# DSM_VB2032-241203_Sch.net
KiCad netlist of a schematic drawn in Altium Designer
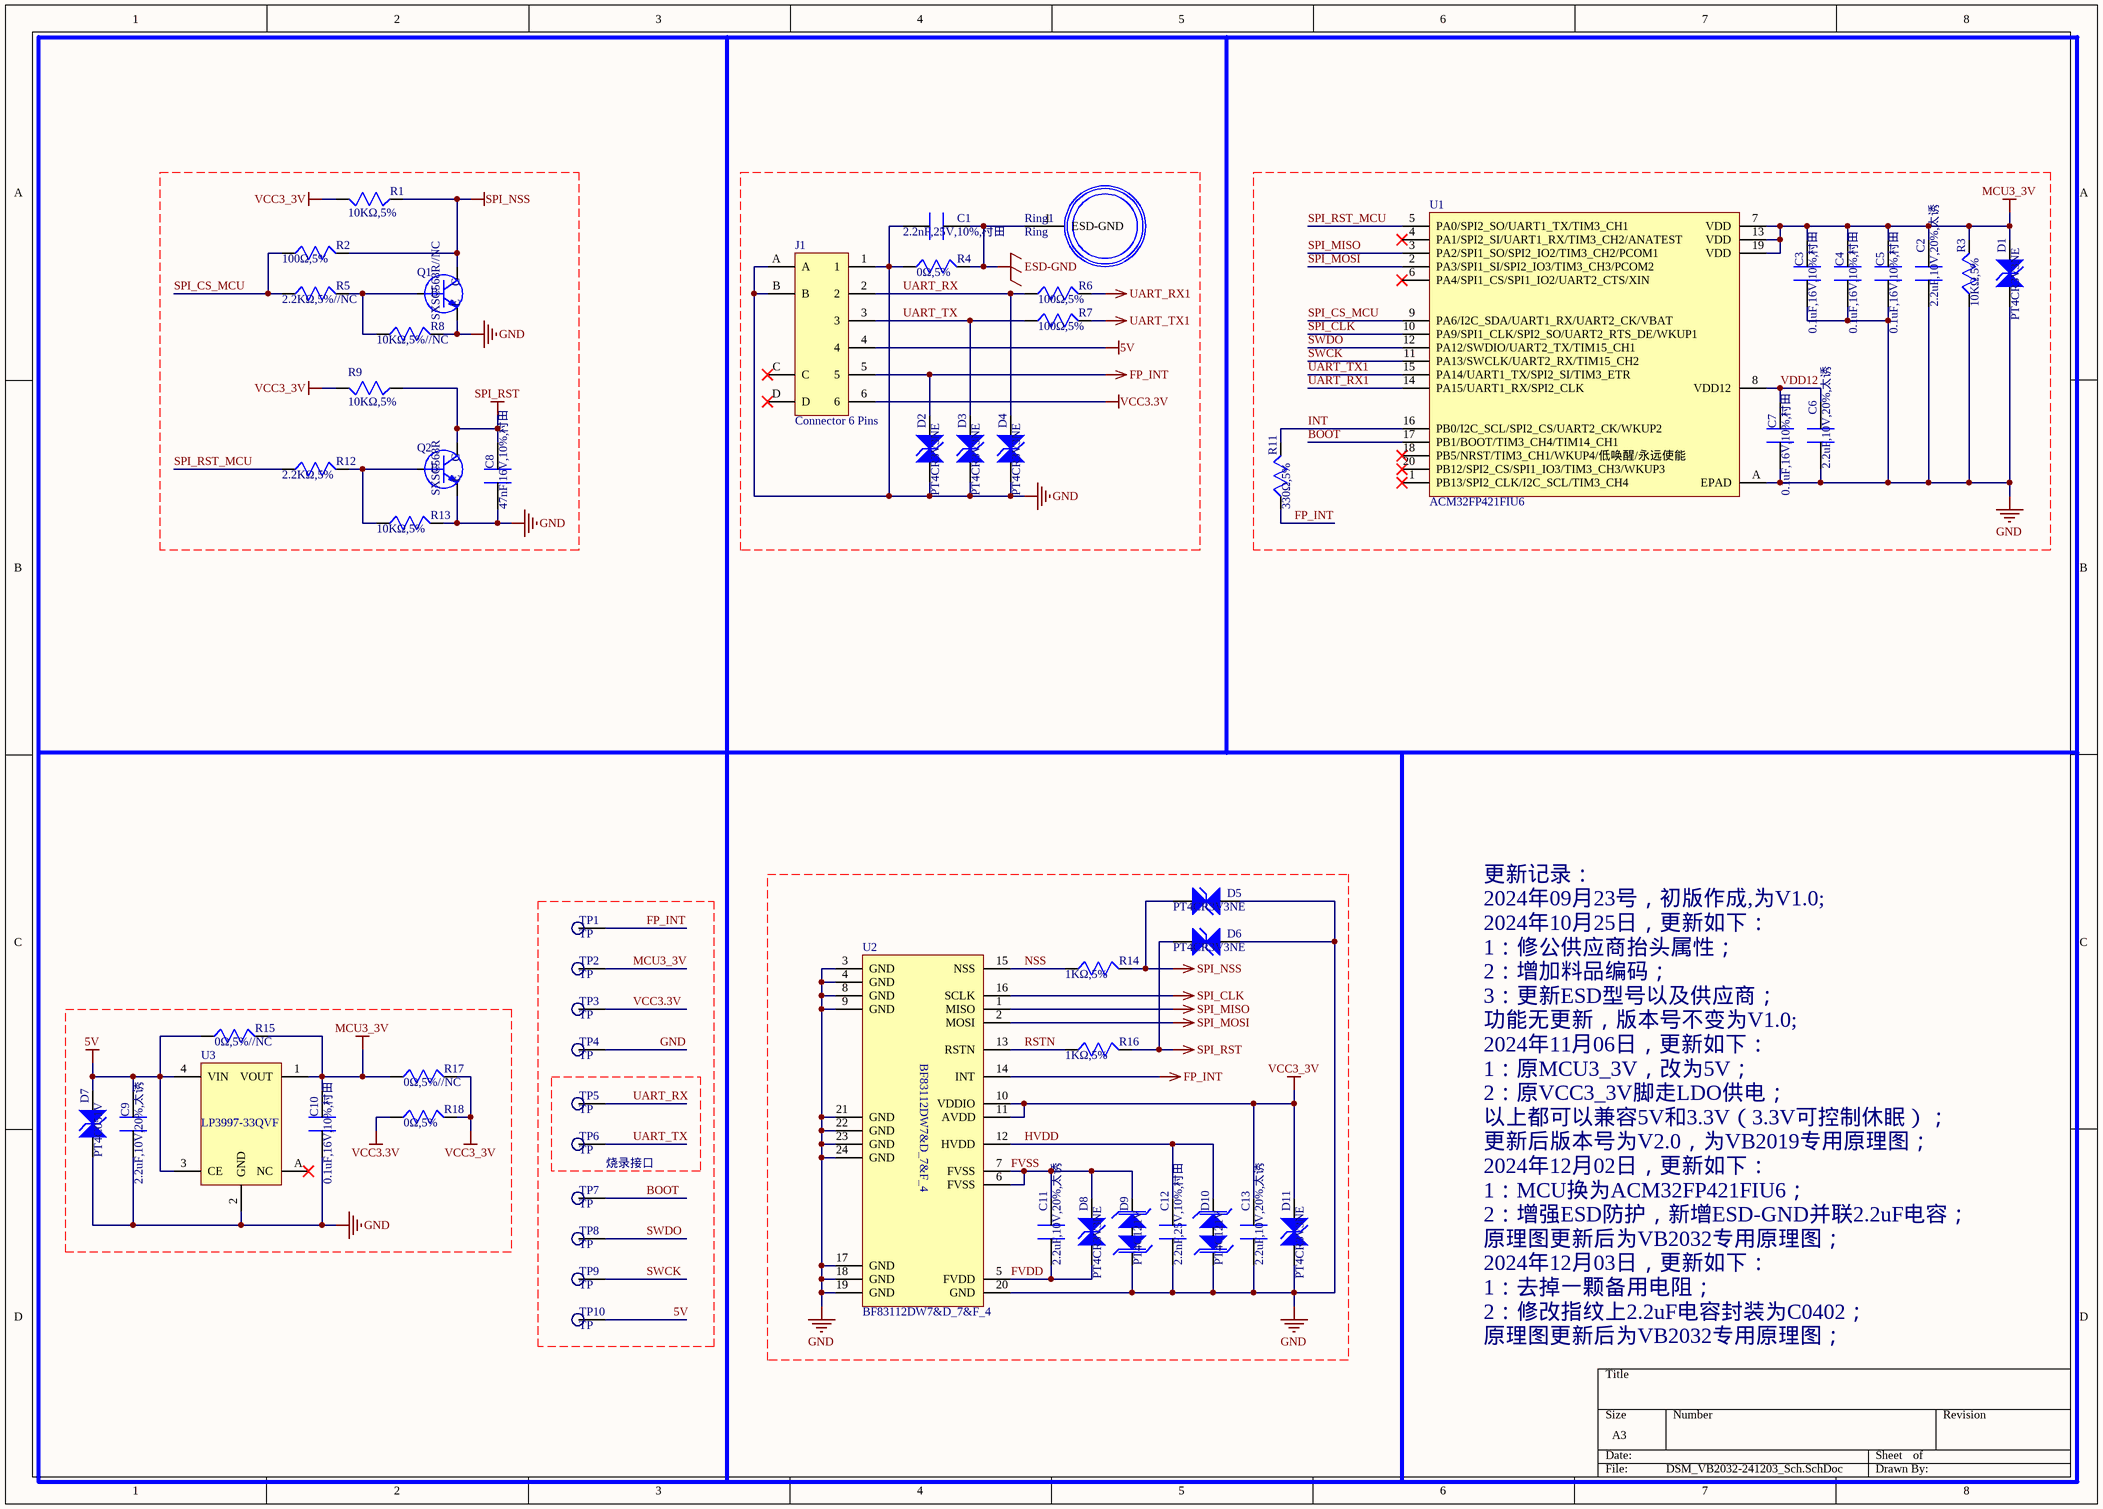
[diagram p0: DSM_VB2032-241203_Sch.SchDoc]

(export (version "E")
  (design (tool "Eeschema 10.0.6"))
  (components
    (comp (ref "C1")
      (value "2.2nF,25V,10%,村田")
      (footprint "C0201")
      (description "贴片电容")
      (libsource (lib "Mkyou") (part "Cap"))
    )
    (comp (ref "C2")
      (value "2.2uF,10V,20%,太诱")
      (footprint "C0201")
      (description "贴片电容")
      (libsource (lib "Mkyou") (part "Cap"))
    )
    (comp (ref "C3")
      (value "0.1uF,16V,10%,村田")
      (footprint "C0201")
      (description "贴片电容")
      (libsource (lib "Mkyou") (part "Cap"))
    )
    (comp (ref "C4")
      (value "0.1uF,16V,10%,村田")
      (footprint "C0201")
      (description "贴片电容")
      (libsource (lib "Mkyou") (part "Cap"))
    )
    (comp (ref "C5")
      (value "0.1uF,16V,10%,村田")
      (footprint "C0201")
      (description "贴片电容")
      (libsource (lib "Mkyou") (part "Cap"))
    )
    (comp (ref "C6")
      (value "2.2uF,10V,20%,太诱")
      (footprint "C0201")
      (description "贴片电容")
      (libsource (lib "Mkyou") (part "Cap"))
    )
    (comp (ref "C7")
      (value "0.1uF,16V,10%,村田")
      (footprint "C0201")
      (description "贴片电容")
      (libsource (lib "Mkyou") (part "Cap"))
    )
    (comp (ref "C8")
      (value "47nF,16V,10%,村田")
      (footprint "C0201")
      (description "贴片电容")
      (libsource (lib "Mkyou") (part "Cap"))
    )
    (comp (ref "C9")
      (value "2.2uF,10V,20%,太诱")
      (footprint "C0201")
      (description "贴片电容")
      (libsource (lib "Mkyou") (part "Cap"))
    )
    (comp (ref "C10")
      (value "0.1uF,16V,10%,村田")
      (footprint "C0201")
      (description "贴片电容")
      (libsource (lib "Mkyou") (part "Cap"))
    )
    (comp (ref "C11")
      (value "2.2uF,10V,20%,太诱")
      (footprint "CC0402-M")
      (description "贴片电容")
      (libsource (lib "Mkyou") (part "Cap"))
    )
    (comp (ref "C12")
      (value "2.2nF,25V,10%,村田")
      (footprint "C0201")
      (description "贴片电容")
      (libsource (lib "Mkyou") (part "Cap"))
    )
    (comp (ref "C13")
      (value "2.2uF,10V,20%,太诱")
      (footprint "CC0402-M")
      (description "贴片电容")
      (libsource (lib "Mkyou") (part "Cap"))
    )
    (comp (ref "D1")
      (value "PT4CR3V3NE")
      (footprint "SOD-962")
      (description "双向静电二极管")
      (libsource (lib "Mkyou") (part "ESD"))
    )
    (comp (ref "D2")
      (value "PT4CR3V3NE")
      (footprint "SOD-962")
      (description "双向静电二极管")
      (libsource (lib "Mkyou") (part "ESD"))
    )
    (comp (ref "D3")
      (value "PT4CR3V3NE")
      (footprint "SOD-962")
      (description "双向静电二极管")
      (libsource (lib "Mkyou") (part "ESD"))
    )
    (comp (ref "D4")
      (value "PT4CR3V3NE")
      (footprint "SOD-962")
      (description "双向静电二极管")
      (libsource (lib "Mkyou") (part "ESD"))
    )
    (comp (ref "D5")
      (value "PT4CR3V3NE")
      (footprint "SOD-962")
      (description "双向静电二极管")
      (libsource (lib "Mkyou") (part "ESD"))
    )
    (comp (ref "D6")
      (value "PT4CR3V3NE")
      (footprint "SOD-962")
      (description "双向静电二极管")
      (libsource (lib "Mkyou") (part "ESD"))
    )
    (comp (ref "D7")
      (value "PT4C051V")
      (footprint "DFN0603-2L 0.3*0.23 Pitch 0.38")
      (description "双向静电二极管")
      (libsource (lib "Mkyou") (part "ESD"))
    )
    (comp (ref "D8")
      (value "PT4CR3V3NE")
      (footprint "SOD-962")
      (description "双向静电二极管")
      (libsource (lib "Mkyou") (part "ESD"))
    )
    (comp (ref "D9")
      (value "PT4C121V")
      (footprint "SOD-962")
      (description "双向瞬态抑制二极管")
      (libsource (lib "Mkyou") (part "TVS"))
    )
    (comp (ref "D10")
      (value "PT4C121V")
      (footprint "SOD-962")
      (description "双向瞬态抑制二极管")
      (libsource (lib "Mkyou") (part "TVS"))
    )
    (comp (ref "D11")
      (value "PT4CR3V3NE")
      (footprint "SOD-962")
      (description "双向静电二极管")
      (libsource (lib "Mkyou") (part "ESD"))
    )
    (comp (ref "J1")
      (value "Connector 6 Pins")
      (footprint "A1004LF-06A")
      (description "连接器")
      (libsource (lib "Mkyou") (part "Connector 6 Pins"))
    )
    (comp (ref "Q1")
      (value "SXSC568R//NC")
      (footprint "SOT-723")
      (description "NPN型三极管")
      (libsource (lib "Mkyou") (part "NPN BCE"))
    )
    (comp (ref "Q2")
      (value "SXSC568R")
      (footprint "SOT-723")
      (description "NPN型三极管")
      (libsource (lib "Mkyou") (part "NPN BCE"))
    )
    (comp (ref "R1")
      (value "10KΩ,5%")
      (footprint "R0201")
      (description "贴片电阻")
      (libsource (lib "Mkyou") (part "RES"))
    )
    (comp (ref "R2")
      (value "100Ω,5%")
      (footprint "R0201")
      (description "贴片电阻")
      (libsource (lib "Mkyou") (part "RES"))
    )
    (comp (ref "R3")
      (value "10KΩ,5%")
      (footprint "R0201")
      (description "贴片电阻")
      (libsource (lib "Mkyou") (part "RES"))
    )
    (comp (ref "R4")
      (value "0Ω,5%")
      (footprint "R0201")
      (description "贴片电阻")
      (libsource (lib "Mkyou") (part "RES"))
    )
    (comp (ref "R5")
      (value "2.2KΩ,5%//NC")
      (footprint "R0201")
      (description "贴片电阻")
      (libsource (lib "Mkyou") (part "RES"))
    )
    (comp (ref "R6")
      (value "100Ω,5%")
      (footprint "R0201")
      (description "贴片电阻")
      (libsource (lib "Mkyou") (part "RES"))
    )
    (comp (ref "R7")
      (value "100Ω,5%")
      (footprint "R0201")
      (description "贴片电阻")
      (libsource (lib "Mkyou") (part "RES"))
    )
    (comp (ref "R8")
      (value "10KΩ,5%//NC")
      (footprint "R0201")
      (description "贴片电阻")
      (libsource (lib "Mkyou") (part "RES"))
    )
    (comp (ref "R9")
      (value "10KΩ,5%")
      (footprint "R0201")
      (description "贴片电阻")
      (libsource (lib "Mkyou") (part "RES"))
    )
    (comp (ref "R11")
      (value "330Ω,5%")
      (footprint "R0201")
      (description "贴片电阻")
      (libsource (lib "Mkyou") (part "RES"))
    )
    (comp (ref "R12")
      (value "2.2KΩ,5%")
      (footprint "R0201")
      (description "贴片电阻")
      (libsource (lib "Mkyou") (part "RES"))
    )
    (comp (ref "R13")
      (value "10KΩ,5%")
      (footprint "R0201")
      (description "贴片电阻")
      (libsource (lib "Mkyou") (part "RES"))
    )
    (comp (ref "R14")
      (value "1KΩ,5%")
      (footprint "R0201")
      (description "贴片电阻")
      (libsource (lib "Mkyou") (part "RES"))
    )
    (comp (ref "R15")
      (value "0Ω,5%//NC")
      (footprint "R0201")
      (description "贴片电阻")
      (libsource (lib "Mkyou") (part "RES"))
    )
    (comp (ref "R16")
      (value "1KΩ,5%")
      (footprint "R0201")
      (description "贴片电阻")
      (libsource (lib "Mkyou") (part "RES"))
    )
    (comp (ref "R17")
      (value "0Ω,5%//NC")
      (footprint "R0201")
      (description "贴片电阻")
      (libsource (lib "Mkyou") (part "RES"))
    )
    (comp (ref "R18")
      (value "0Ω,5%")
      (footprint "R0201")
      (description "贴片电阻")
      (libsource (lib "Mkyou") (part "RES"))
    )
    (comp (ref "Ring1")
      (value "Ring")
      (footprint "Ring")
      (description "金属环")
      (libsource (lib "Mkyou") (part "Ring"))
    )
    (comp (ref "TP1")
      (value "TP")
      (footprint "TP（Φ0.5）")
      (description "非正常物料无需采购")
      (libsource (lib "Mkyou") (part "TP"))
    )
    (comp (ref "TP2")
      (value "TP")
      (footprint "TP（Φ0.5）")
      (description "非正常物料无需采购")
      (libsource (lib "Mkyou") (part "TP"))
    )
    (comp (ref "TP3")
      (value "TP")
      (footprint "TP（Φ0.5）")
      (description "非正常物料无需采购")
      (libsource (lib "Mkyou") (part "TP"))
    )
    (comp (ref "TP4")
      (value "TP")
      (footprint "TP（Φ0.5）")
      (description "非正常物料无需采购")
      (libsource (lib "Mkyou") (part "TP"))
    )
    (comp (ref "TP5")
      (value "TP")
      (footprint "TP（Φ0.5）")
      (description "非正常物料无需采购")
      (libsource (lib "Mkyou") (part "TP"))
    )
    (comp (ref "TP6")
      (value "TP")
      (footprint "TP（Φ0.5）")
      (description "非正常物料无需采购")
      (libsource (lib "Mkyou") (part "TP"))
    )
    (comp (ref "TP7")
      (value "TP")
      (footprint "TP（Φ0.5）")
      (description "非正常物料无需采购")
      (libsource (lib "Mkyou") (part "TP"))
    )
    (comp (ref "TP8")
      (value "TP")
      (footprint "TP（Φ0.5）")
      (description "非正常物料无需采购")
      (libsource (lib "Mkyou") (part "TP"))
    )
    (comp (ref "TP9")
      (value "TP")
      (footprint "TP（Φ0.5）")
      (description "非正常物料无需采购")
      (libsource (lib "Mkyou") (part "TP"))
    )
    (comp (ref "TP10")
      (value "TP")
      (footprint "TP（Φ0.5）")
      (description "非正常物料无需采购")
      (libsource (lib "Mkyou") (part "TP"))
    )
    (comp (ref "U1")
      (value "ACM32FP421FIU6")
      (footprint "QFN 20 3*3 Pitch 0.4")
      (description "微控制单元")
      (libsource (lib "Mkyou") (part "ACM32FP421"))
    )
    (comp (ref "U2")
      (value "BF83112DW7&D_7&F_4")
      (footprint "BF83112DW7&D_7&F_4")
      (description "电容按压式指纹识别芯片")
      (libsource (lib "Mkyou") (part "BF83112DW7&D_7&F_4"))
    )
    (comp (ref "U3")
      (value "LP3997-33QVF")
      (footprint "DFN 1*1-4L")
      (description "线性稳压器")
      (libsource (lib "Mkyou") (part "LDO 4 Pins"))
    )
  )
  (nets
    (net (code "1") (name "/BOOT") (class "Default")
      (node (ref "TP7") (pin "1") (pinfunction "1_1") (pintype "passive"))
      (node (ref "U1") (pin "17") (pinfunction "PB1/BOOT/TIM3_CH4/TIM14_CH1_17") (pintype "passive"))
    )
    (net (code "2") (name "/FVDD") (class "Default")
      (node (ref "C11") (pin "1") (pinfunction "1_1") (pintype "passive"))
      (node (ref "D8") (pin "1") (pinfunction "1_1") (pintype "passive"))
      (node (ref "U2") (pin "5") (pinfunction "FVDD_5") (pintype "passive"))
    )
    (net (code "3") (name "/FVSS") (class "Default")
      (node (ref "C11") (pin "2") (pinfunction "2_2") (pintype "passive"))
      (node (ref "D8") (pin "2") (pinfunction "2_2") (pintype "passive"))
      (node (ref "D9") (pin "1") (pinfunction "1_1") (pintype "passive"))
      (node (ref "U2") (pin "6") (pinfunction "FVSS_6") (pintype "passive"))
      (node (ref "U2") (pin "7") (pinfunction "FVSS_7") (pintype "passive"))
    )
    (net (code "4") (name "/HVDD") (class "Default")
      (node (ref "C12") (pin "2") (pinfunction "2_2") (pintype "passive"))
      (node (ref "D10") (pin "1") (pinfunction "1_1") (pintype "passive"))
      (node (ref "U2") (pin "12") (pinfunction "HVDD_12") (pintype "passive"))
    )
    (net (code "5") (name "/INT") (class "Default")
      (node (ref "R11") (pin "2") (pinfunction "2_2") (pintype "passive"))
      (node (ref "U1") (pin "16") (pinfunction "PB0/I2C_SCL/SPI2_CS/UART2_CK/WKUP2_16") (pintype "passive"))
    )
    (net (code "6") (name "/NSS") (class "Default")
      (node (ref "R14") (pin "1") (pinfunction "1_1") (pintype "passive"))
      (node (ref "U2") (pin "15") (pinfunction "NSS_15") (pintype "passive"))
    )
    (net (code "7") (name "/RSTN") (class "Default")
      (node (ref "R16") (pin "1") (pinfunction "1_1") (pintype "passive"))
      (node (ref "U2") (pin "13") (pinfunction "RSTN_13") (pintype "passive"))
    )
    (net (code "8") (name "/SPI_CS_MCU") (class "Default")
      (node (ref "R2") (pin "1") (pinfunction "1_1") (pintype "passive"))
      (node (ref "R5") (pin "1") (pinfunction "1_1") (pintype "passive"))
      (node (ref "U1") (pin "9") (pinfunction "PA6/I2C_SDA/UART1_RX/UART2_CK/VBAT_9") (pintype "passive"))
    )
    (net (code "9") (name "/SPI_RST_MCU") (class "Default")
      (node (ref "R12") (pin "1") (pinfunction "1_1") (pintype "passive"))
      (node (ref "U1") (pin "5") (pinfunction "PA0/SPI2_SO/UART1_TX/TIM3_CH1_5") (pintype "passive"))
    )
    (net (code "10") (name "/SWCK") (class "Default")
      (node (ref "TP9") (pin "1") (pinfunction "1_1") (pintype "passive"))
      (node (ref "U1") (pin "11") (pinfunction "PA13/SWCLK/UART2_RX/TIM15_CH2_11") (pintype "passive"))
    )
    (net (code "11") (name "/SWDO") (class "Default")
      (node (ref "TP8") (pin "1") (pinfunction "1_1") (pintype "passive"))
      (node (ref "U1") (pin "12") (pinfunction "PA12/SWDIO/UART2_TX/TIM15_CH1_12") (pintype "passive"))
    )
    (net (code "12") (name "/UART_RX") (class "Default")
      (node (ref "D4") (pin "2") (pinfunction "2_2") (pintype "passive"))
      (node (ref "J1") (pin "2") (pinfunction "2_2") (pintype "passive"))
      (node (ref "R6") (pin "1") (pinfunction "1_1") (pintype "passive"))
      (node (ref "TP5") (pin "1") (pinfunction "1_1") (pintype "passive"))
    )
    (net (code "13") (name "/UART_TX") (class "Default")
      (node (ref "D3") (pin "2") (pinfunction "2_2") (pintype "passive"))
      (node (ref "J1") (pin "3") (pinfunction "3_3") (pintype "passive"))
      (node (ref "R7") (pin "1") (pinfunction "1_1") (pintype "passive"))
      (node (ref "TP6") (pin "1") (pinfunction "1_1") (pintype "passive"))
    )
    (net (code "14") (name "/VDD12") (class "Default")
      (node (ref "C6") (pin "2") (pinfunction "2_2") (pintype "passive"))
      (node (ref "C7") (pin "2") (pinfunction "2_2") (pintype "passive"))
      (node (ref "U1") (pin "8") (pinfunction "VDD12_8") (pintype "passive"))
    )
    (net (code "15") (name "5V") (class "Default")
      (node (ref "C9") (pin "2") (pinfunction "2_2") (pintype "passive"))
      (node (ref "D7") (pin "2") (pinfunction "2_2") (pintype "passive"))
      (node (ref "J1") (pin "4") (pinfunction "4_4") (pintype "passive"))
      (node (ref "R15") (pin "1") (pinfunction "1_1") (pintype "passive"))
      (node (ref "TP10") (pin "1") (pinfunction "1_1") (pintype "passive"))
      (node (ref "U3") (pin "3") (pinfunction "CE_3") (pintype "passive"))
      (node (ref "U3") (pin "4") (pinfunction "VIN_4") (pintype "passive"))
    )
    (net (code "16") (name "ESD-GND") (class "Default")
      (node (ref "C1") (pin "1") (pinfunction "1_1") (pintype "passive"))
      (node (ref "R4") (pin "2") (pinfunction "2_2") (pintype "passive"))
      (node (ref "Ring1") (pin "1") (pinfunction "ESD-GND_1") (pintype "passive"))
    )
    (net (code "17") (name "FP_INT") (class "Default")
      (node (ref "D2") (pin "2") (pinfunction "2_2") (pintype "passive"))
      (node (ref "J1") (pin "5") (pinfunction "5_5") (pintype "passive"))
      (node (ref "R11") (pin "1") (pinfunction "1_1") (pintype "passive"))
      (node (ref "TP1") (pin "1") (pinfunction "1_1") (pintype "passive"))
      (node (ref "U2") (pin "14") (pinfunction "INT_14") (pintype "passive"))
    )
    (net (code "18") (name "GND") (class "Default")
      (node (ref "C1") (pin "2") (pinfunction "2_2") (pintype "passive"))
      (node (ref "C10") (pin "1") (pinfunction "1_1") (pintype "passive"))
      (node (ref "C12") (pin "1") (pinfunction "1_1") (pintype "passive"))
      (node (ref "C13") (pin "1") (pinfunction "1_1") (pintype "passive"))
      (node (ref "C2") (pin "1") (pinfunction "1_1") (pintype "passive"))
      (node (ref "C3") (pin "1") (pinfunction "1_1") (pintype "passive"))
      (node (ref "C4") (pin "1") (pinfunction "1_1") (pintype "passive"))
      (node (ref "C5") (pin "1") (pinfunction "1_1") (pintype "passive"))
      (node (ref "C6") (pin "1") (pinfunction "1_1") (pintype "passive"))
      (node (ref "C7") (pin "1") (pinfunction "1_1") (pintype "passive"))
      (node (ref "C8") (pin "1") (pinfunction "1_1") (pintype "passive"))
      (node (ref "C9") (pin "1") (pinfunction "1_1") (pintype "passive"))
      (node (ref "D1") (pin "1") (pinfunction "1_1") (pintype "passive"))
      (node (ref "D10") (pin "2") (pinfunction "2_2") (pintype "passive"))
      (node (ref "D11") (pin "1") (pinfunction "1_1") (pintype "passive"))
      (node (ref "D2") (pin "1") (pinfunction "1_1") (pintype "passive"))
      (node (ref "D3") (pin "1") (pinfunction "1_1") (pintype "passive"))
      (node (ref "D4") (pin "1") (pinfunction "1_1") (pintype "passive"))
      (node (ref "D5") (pin "1") (pinfunction "1_1") (pintype "passive"))
      (node (ref "D6") (pin "1") (pinfunction "1_1") (pintype "passive"))
      (node (ref "D7") (pin "1") (pinfunction "1_1") (pintype "passive"))
      (node (ref "D9") (pin "2") (pinfunction "2_2") (pintype "passive"))
      (node (ref "J1") (pin "1") (pinfunction "1_1") (pintype "passive"))
      (node (ref "J1") (pin "A") (pinfunction "A_A") (pintype "passive"))
      (node (ref "J1") (pin "B") (pinfunction "B_B") (pintype "passive"))
      (node (ref "Q1") (pin "2") (pinfunction "E_2") (pintype "passive"))
      (node (ref "Q2") (pin "2") (pinfunction "E_2") (pintype "passive"))
      (node (ref "R13") (pin "2") (pinfunction "2_2") (pintype "passive"))
      (node (ref "R3") (pin "1") (pinfunction "1_1") (pintype "passive"))
      (node (ref "R4") (pin "1") (pinfunction "1_1") (pintype "passive"))
      (node (ref "R8") (pin "2") (pinfunction "2_2") (pintype "passive"))
      (node (ref "TP4") (pin "1") (pinfunction "1_1") (pintype "passive"))
      (node (ref "U1") (pin "A") (pinfunction "EPAD_A") (pintype "passive"))
      (node (ref "U2") (pin "17") (pinfunction "GND_17") (pintype "passive"))
      (node (ref "U2") (pin "18") (pinfunction "GND_18") (pintype "passive"))
      (node (ref "U2") (pin "19") (pinfunction "GND_19") (pintype "passive"))
      (node (ref "U2") (pin "20") (pinfunction "GND_20") (pintype "passive"))
      (node (ref "U2") (pin "21") (pinfunction "GND_21") (pintype "passive"))
      (node (ref "U2") (pin "22") (pinfunction "GND_22") (pintype "passive"))
      (node (ref "U2") (pin "23") (pinfunction "GND_23") (pintype "passive"))
      (node (ref "U2") (pin "24") (pinfunction "GND_24") (pintype "passive"))
      (node (ref "U2") (pin "3") (pinfunction "GND_3") (pintype "passive"))
      (node (ref "U2") (pin "4") (pinfunction "GND_4") (pintype "passive"))
      (node (ref "U2") (pin "8") (pinfunction "GND_8") (pintype "passive"))
      (node (ref "U2") (pin "9") (pinfunction "GND_9") (pintype "passive"))
      (node (ref "U3") (pin "2") (pinfunction "GND_2") (pintype "passive"))
    )
    (net (code "19") (name "MCU3_3V") (class "Default")
      (node (ref "C10") (pin "2") (pinfunction "2_2") (pintype "passive"))
      (node (ref "C2") (pin "2") (pinfunction "2_2") (pintype "passive"))
      (node (ref "C3") (pin "2") (pinfunction "2_2") (pintype "passive"))
      (node (ref "C4") (pin "2") (pinfunction "2_2") (pintype "passive"))
      (node (ref "C5") (pin "2") (pinfunction "2_2") (pintype "passive"))
      (node (ref "D1") (pin "2") (pinfunction "2_2") (pintype "passive"))
      (node (ref "R15") (pin "2") (pinfunction "2_2") (pintype "passive"))
      (node (ref "R17") (pin "1") (pinfunction "1_1") (pintype "passive"))
      (node (ref "R3") (pin "2") (pinfunction "2_2") (pintype "passive"))
      (node (ref "TP2") (pin "1") (pinfunction "1_1") (pintype "passive"))
      (node (ref "U1") (pin "13") (pinfunction "VDD_13") (pintype "passive"))
      (node (ref "U1") (pin "19") (pinfunction "VDD_19") (pintype "passive"))
      (node (ref "U1") (pin "7") (pinfunction "VDD_7") (pintype "passive"))
      (node (ref "U3") (pin "1") (pinfunction "VOUT_1") (pintype "passive"))
    )
    (net (code "20") (name "Net-(Q1-B)") (class "Default")
      (node (ref "Q1") (pin "1") (pinfunction "B_1") (pintype "passive"))
      (node (ref "R5") (pin "2") (pinfunction "2_2") (pintype "passive"))
      (node (ref "R8") (pin "1") (pinfunction "1_1") (pintype "passive"))
    )
    (net (code "21") (name "Net-(Q2-B)") (class "Default")
      (node (ref "Q2") (pin "1") (pinfunction "B_1") (pintype "passive"))
      (node (ref "R12") (pin "2") (pinfunction "2_2") (pintype "passive"))
      (node (ref "R13") (pin "1") (pinfunction "1_1") (pintype "passive"))
    )
    (net (code "22") (name "SPI_CLK") (class "Default")
      (node (ref "U1") (pin "10") (pinfunction "PA9/SPI1_CLK/SPI2_SO/UART2_RTS_DE/WKUP1_10") (pintype "passive"))
      (node (ref "U2") (pin "16") (pinfunction "SCLK_16") (pintype "passive"))
    )
    (net (code "23") (name "SPI_MISO") (class "Default")
      (node (ref "U1") (pin "3") (pinfunction "PA2/SPI1_SO/SPI2_IO2/TIM3_CH2/PCOM1_3") (pintype "passive"))
      (node (ref "U2") (pin "1") (pinfunction "MISO_1") (pintype "passive"))
    )
    (net (code "24") (name "SPI_MOSI") (class "Default")
      (node (ref "U1") (pin "2") (pinfunction "PA3/SPI1_SI/SPI2_IO3/TIM3_CH3/PCOM2_2") (pintype "passive"))
      (node (ref "U2") (pin "2") (pinfunction "MOSI_2") (pintype "passive"))
    )
    (net (code "25") (name "SPI_NSS") (class "Default")
      (node (ref "D5") (pin "2") (pinfunction "2_2") (pintype "passive"))
      (node (ref "Q1") (pin "3") (pinfunction "C_3") (pintype "passive"))
      (node (ref "R1") (pin "1") (pinfunction "1_1") (pintype "passive"))
      (node (ref "R14") (pin "2") (pinfunction "2_2") (pintype "passive"))
      (node (ref "R2") (pin "2") (pinfunction "2_2") (pintype "passive"))
    )
    (net (code "26") (name "SPI_RST") (class "Default")
      (node (ref "C8") (pin "2") (pinfunction "2_2") (pintype "passive"))
      (node (ref "D6") (pin "2") (pinfunction "2_2") (pintype "passive"))
      (node (ref "Q2") (pin "3") (pinfunction "C_3") (pintype "passive"))
      (node (ref "R16") (pin "2") (pinfunction "2_2") (pintype "passive"))
      (node (ref "R9") (pin "1") (pinfunction "1_1") (pintype "passive"))
    )
    (net (code "27") (name "UART_RX1") (class "Default")
      (node (ref "R6") (pin "2") (pinfunction "2_2") (pintype "passive"))
      (node (ref "U1") (pin "14") (pinfunction "PA15/UART1_RX/SPI2_CLK_14") (pintype "passive"))
    )
    (net (code "28") (name "UART_TX1") (class "Default")
      (node (ref "R7") (pin "2") (pinfunction "2_2") (pintype "passive"))
      (node (ref "U1") (pin "15") (pinfunction "PA14/UART1_TX/SPI2_SI/TIM3_ETR_15") (pintype "passive"))
    )
    (net (code "29") (name "VCC3.3V") (class "Default")
      (node (ref "J1") (pin "6") (pinfunction "6_6") (pintype "passive"))
      (node (ref "R18") (pin "1") (pinfunction "1_1") (pintype "passive"))
      (node (ref "TP3") (pin "1") (pinfunction "1_1") (pintype "passive"))
    )
    (net (code "30") (name "VCC3_3V") (class "Default")
      (node (ref "C13") (pin "2") (pinfunction "2_2") (pintype "passive"))
      (node (ref "D11") (pin "2") (pinfunction "2_2") (pintype "passive"))
      (node (ref "R1") (pin "2") (pinfunction "2_2") (pintype "passive"))
      (node (ref "R17") (pin "2") (pinfunction "2_2") (pintype "passive"))
      (node (ref "R18") (pin "2") (pinfunction "2_2") (pintype "passive"))
      (node (ref "R9") (pin "2") (pinfunction "2_2") (pintype "passive"))
      (node (ref "U2") (pin "10") (pinfunction "VDDIO_10") (pintype "passive"))
      (node (ref "U2") (pin "11") (pinfunction "AVDD_11") (pintype "passive"))
    )
    (net (code "31") (name "unconnected-(J1-PadC)") (class "Default")
      (node (ref "J1") (pin "C") (pinfunction "C_C") (pintype "passive+no_connect"))
    )
    (net (code "32") (name "unconnected-(J1-PadD)") (class "Default")
      (node (ref "J1") (pin "D") (pinfunction "D_D") (pintype "passive+no_connect"))
    )
    (net (code "33") (name "unconnected-(U1-PA1{slash}SPI2_SI{slash}UART1_RX{slash}TIM3_CH2{slash}ANATEST-Pad4)") (class "Default")
      (node (ref "U1") (pin "4") (pinfunction "PA1/SPI2_SI/UART1_RX/TIM3_CH2/ANATEST_4") (pintype "passive+no_connect"))
    )
    (net (code "34") (name "unconnected-(U1-PA4{slash}SPI1_CS{slash}SPI1_IO2{slash}UART2_CTS{slash}XIN-Pad6)") (class "Default")
      (node (ref "U1") (pin "6") (pinfunction "PA4/SPI1_CS/SPI1_IO2/UART2_CTS/XIN_6") (pintype "passive+no_connect"))
    )
    (net (code "35") (name "unconnected-(U1-PB5{slash}NRST{slash}TIM3_CH1{slash}WKUP4{slash}低唤醒{slash}永远使能-Pad18)") (class "Default")
      (node (ref "U1") (pin "18") (pinfunction "PB5/NRST/TIM3_CH1/WKUP4/低唤醒/永远使能_18") (pintype "passive+no_connect"))
    )
    (net (code "36") (name "unconnected-(U1-PB12{slash}SPI2_CS{slash}SPI1_IO3{slash}TIM3_CH3{slash}WKUP3-Pad20)") (class "Default")
      (node (ref "U1") (pin "20") (pinfunction "PB12/SPI2_CS/SPI1_IO3/TIM3_CH3/WKUP3_20") (pintype "passive+no_connect"))
    )
    (net (code "37") (name "unconnected-(U1-PB13{slash}SPI2_CLK{slash}I2C_SCL{slash}TIM3_CH4-Pad1)") (class "Default")
      (node (ref "U1") (pin "1") (pinfunction "PB13/SPI2_CLK/I2C_SCL/TIM3_CH4_1") (pintype "passive+no_connect"))
    )
    (net (code "38") (name "unconnected-(U3-NC-PadA)") (class "Default")
      (node (ref "U3") (pin "A") (pinfunction "NC_A") (pintype "passive+no_connect"))
    )
  )
)
